# Analog_Signal_Cond.net
KiCad netlist of a schematic drawn in Altium Designer
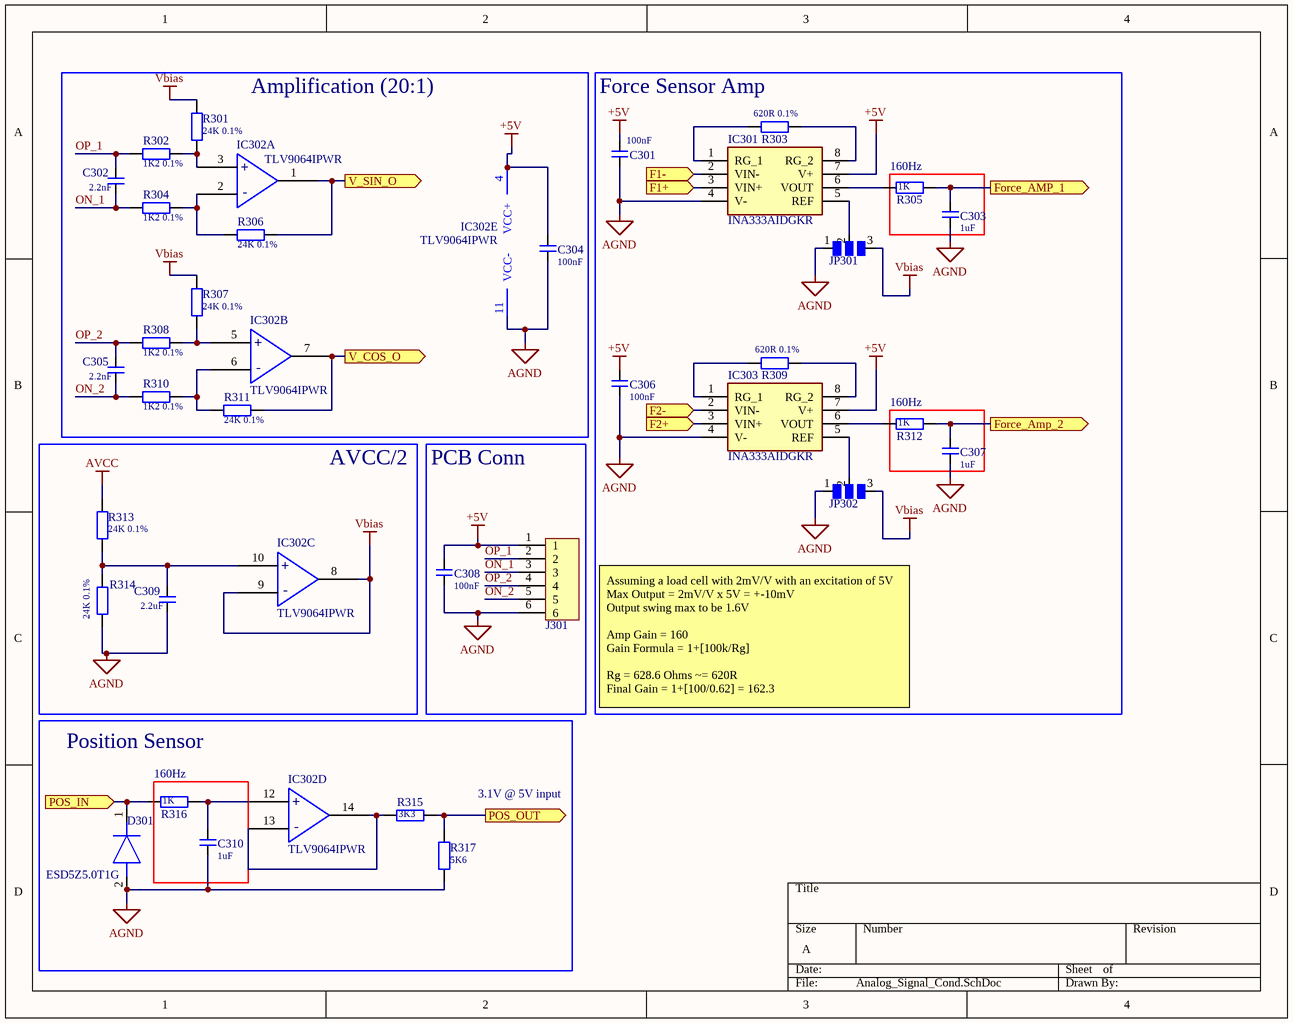
[diagram p0: Analog_Signal_Cond.SchDoc]

(export (version "E")
  (design (tool "Eeschema 10.0.6"))
  (components
    (comp (ref "C301")
      (value "100nF")
      (footprint "CAPC1005X06N")
      (description "Capacitor")
      (fields (field (name "MPN") "GCM155R71H104KE02D") (field (name "Comment") "Cap"))
      (libsource (lib "SamacSys") (part "Cap"))
    )
    (comp (ref "C302")
      (value "2.2nF")
      (footprint "CAPC1608X09N")
      (description "Capacitor")
      (fields (field (name "MPN") "CC0603KRX7R9BB222") (field (name "Comment") "Cap"))
      (libsource (lib "SamacSys") (part "Cap"))
    )
    (comp (ref "C303")
      (value "1uF")
      (footprint "CAPC1005X06N")
      (description "Capacitor")
      (fields (field (name "MPN") "GRM155Z71A105KE01D") (field (name "Comment") "Cap"))
      (libsource (lib "SamacSys") (part "Cap"))
    )
    (comp (ref "C304")
      (value "100nF")
      (footprint "CAPC1005X06N")
      (description "Capacitor")
      (fields (field (name "MPN") "GCM155R71H104KE02D") (field (name "Comment") "Cap"))
      (libsource (lib "SamacSys") (part "Cap"))
    )
    (comp (ref "C305")
      (value "2.2nF")
      (footprint "CAPC1608X09N")
      (description "Capacitor")
      (fields (field (name "MPN") "CC0603KRX7R9BB222") (field (name "Comment") "Cap"))
      (libsource (lib "SamacSys") (part "Cap"))
    )
    (comp (ref "C306")
      (value "100nF")
      (footprint "CAPC1005X06N")
      (description "Capacitor")
      (fields (field (name "MPN") "GCM155R71H104KE02D") (field (name "Comment") "Cap"))
      (libsource (lib "SamacSys") (part "Cap"))
    )
    (comp (ref "C307")
      (value "1uF")
      (footprint "CAPC1005X06N")
      (description "Capacitor")
      (fields (field (name "MPN") "GRM155Z71A105KE01D") (field (name "Comment") "Cap"))
      (libsource (lib "SamacSys") (part "Cap"))
    )
    (comp (ref "C308")
      (value "100nF")
      (footprint "CAPC1005X06N")
      (description "Capacitor")
      (fields (field (name "MPN") "GCM155R71H104KE02D") (field (name "Comment") "Cap"))
      (libsource (lib "SamacSys") (part "Cap"))
    )
    (comp (ref "C309")
      (value "2.2uF")
      (footprint "CAPC1005X06N")
      (description "Capacitor")
      (fields (field (name "MPN") "GRM155Z71A225KE44D") (field (name "Comment") "Cap"))
      (libsource (lib "SamacSys") (part "Cap"))
    )
    (comp (ref "C310")
      (value "1uF")
      (footprint "CAPC1005X06N")
      (description "Capacitor")
      (fields (field (name "MPN") "GRM155Z71A105KE01D") (field (name "Comment") "Cap"))
      (libsource (lib "SamacSys") (part "Cap"))
    )
    (comp (ref "D301")
      (value "ESD5Z5.0T1G")
      (footprint "SamacSys:SODFL1608X70N")
      (description "Diode")
      (fields (field (name "MOUSER PART NUMBER") "863-ESD5Z5.0T1G"))
      (libsource (lib "SamacSys") (part "ESD5Z5.0T1G"))
    )
    (comp (ref "IC301")
      (value "INA333AIDGKR")
      (footprint "SamacSys:SOP65P490X110-8N")
      (description "Integrated Circuit")
      (fields (field (name "MOUSER PART NUMBER") "595-INA333AIDGKR"))
      (libsource (lib "*") (part "INA333AIDGKR"))
    )
    (comp (ref "IC302")
      (value "TLV9064IPWR")
      (footprint "SamacSys:SOP65P640X120-14N")
      (description "Integrated Circuit")
      (fields (field (name "MOUSER PART NUMBER") "595-TLV9064IPWR"))
      (libsource (lib "SamacSys") (part "TLV9064IPWR"))
    )
    (comp (ref "IC303")
      (value "INA333AIDGKR")
      (footprint "SamacSys:SOP65P490X110-8N")
      (description "Integrated Circuit")
      (fields (field (name "MOUSER PART NUMBER") "595-INA333AIDGKR"))
      (libsource (lib "*") (part "INA333AIDGKR"))
    )
    (comp (ref "J301")
      (value "PCB_Conn_6P")
      (footprint "PCB_CONN_6")
      (libsource (lib "SamacSys") (part "PCB_Conn_6P"))
    )
    (comp (ref "JP301")
      (value "Jumper_3")
      (footprint "Jumper_3")
      (libsource (lib "SamacSys") (part "Jumper_3"))
    )
    (comp (ref "JP302")
      (value "Jumper_3")
      (footprint "Jumper_3")
      (libsource (lib "SamacSys") (part "Jumper_3"))
    )
    (comp (ref "R301")
      (value "24K 0.1%")
      (footprint "RESC1005X04N")
      (description "Resistor")
      (fields (field (name "MPN") "AR02BTD2402") (field (name "Comment") "R"))
      (libsource (lib "SamacSys") (part "R"))
    )
    (comp (ref "R302")
      (value "1K2 0.1%")
      (footprint "RESC1005X04N")
      (description "Resistor")
      (fields (field (name "MPN") "RT0603BRD071K2L") (field (name "Comment") "R"))
      (libsource (lib "") (part "R_1"))
    )
    (comp (ref "R303")
      (value "620R 0.1%")
      (footprint "RESC1005X04N")
      (description "Resistor")
      (fields (field (name "MPN") "RT0402BRD0710KL") (field (name "Comment") "R"))
      (libsource (lib "") (part "R_1"))
    )
    (comp (ref "R304")
      (value "1K2 0.1%")
      (footprint "RESC1005X04N")
      (description "Resistor")
      (fields (field (name "MPN") "RT0603BRD071K2L") (field (name "Comment") "R"))
      (libsource (lib "") (part "R_1"))
    )
    (comp (ref "R305")
      (value "1K")
      (footprint "RESC1005X04N")
      (description "Resistor")
      (fields (field (name "MPN") "RC0402FR-071KL") (field (name "Comment") "R"))
      (libsource (lib "") (part "R_1"))
    )
    (comp (ref "R306")
      (value "24K 0.1%")
      (footprint "RESC1005X04N")
      (description "Resistor")
      (fields (field (name "MPN") "AR02BTD2402") (field (name "Comment") "R"))
      (libsource (lib "") (part "R_2"))
    )
    (comp (ref "R307")
      (value "24K 0.1%")
      (footprint "RESC1005X04N")
      (description "Resistor")
      (fields (field (name "MPN") "AR02BTD2402") (field (name "Comment") "R"))
      (libsource (lib "") (part "R_3"))
    )
    (comp (ref "R308")
      (value "1K2 0.1%")
      (footprint "RESC1005X04N")
      (description "Resistor")
      (fields (field (name "MPN") "RT0603BRD071K2L") (field (name "Comment") "R"))
      (libsource (lib "") (part "R_1"))
    )
    (comp (ref "R309")
      (value "620R 0.1%")
      (footprint "RESC1005X04N")
      (description "Resistor")
      (fields (field (name "MPN") "RT0402BRD0710KL") (field (name "Comment") "R"))
      (libsource (lib "") (part "R_1"))
    )
    (comp (ref "R310")
      (value "1K2 0.1%")
      (footprint "RESC1005X04N")
      (description "Resistor")
      (fields (field (name "MPN") "RT0603BRD071K2L") (field (name "Comment") "R"))
      (libsource (lib "") (part "R_1"))
    )
    (comp (ref "R311")
      (value "24K 0.1%")
      (footprint "RESC1005X04N")
      (description "Resistor")
      (fields (field (name "MPN") "AR02BTD2402") (field (name "Comment") "R"))
      (libsource (lib "") (part "R_2"))
    )
    (comp (ref "R312")
      (value "1K")
      (footprint "RESC1005X04N")
      (description "Resistor")
      (fields (field (name "MPN") "RC0402FR-071KL") (field (name "Comment") "R"))
      (libsource (lib "") (part "R_1"))
    )
    (comp (ref "R313")
      (value "24K 0.1%")
      (footprint "RESC1005X04N")
      (description "Resistor")
      (fields (field (name "MPN") "AR02BTD2402") (field (name "Comment") "R"))
      (libsource (lib "") (part "R_3"))
    )
    (comp (ref "R314")
      (value "24K 0.1%")
      (footprint "RESC1005X04N")
      (description "Resistor")
      (fields (field (name "MPN") "AR02BTD2402") (field (name "Comment") "R"))
      (libsource (lib "") (part "R_3"))
    )
    (comp (ref "R315")
      (value "3K3")
      (footprint "RESC1005X04N")
      (description "Resistor")
      (fields (field (name "MPN") "RC0402FR-073K3L") (field (name "Comment") "R"))
      (libsource (lib "") (part "R_1"))
    )
    (comp (ref "R316")
      (value "1K")
      (footprint "RESC1005X04N")
      (description "Resistor")
      (fields (field (name "MPN") "RC0402FR-071KL") (field (name "Comment") "R"))
      (libsource (lib "") (part "R_1"))
    )
    (comp (ref "R317")
      (value "5K6")
      (footprint "RESC1005X04N")
      (description "Resistor")
      (fields (field (name "MPN") "RC0402FR-075K6L") (field (name "Comment") "R"))
      (libsource (lib "SamacSys") (part "R"))
    )
  )
  (nets
    (net (code "1") (name "+5V") (class "Default")
      (node (ref "C301") (pin "2") (pinfunction "2_2") (pintype "passive"))
      (node (ref "C304") (pin "2") (pinfunction "2_2") (pintype "passive"))
      (node (ref "C306") (pin "2") (pinfunction "2_2") (pintype "passive"))
      (node (ref "C308") (pin "2") (pinfunction "2_2") (pintype "passive"))
      (node (ref "IC301") (pin "7") (pinfunction "V+_7") (pintype "passive"))
      (node (ref "IC302") (pin "4") (pinfunction "VCC+_4") (pintype "passive"))
      (node (ref "IC303") (pin "7") (pinfunction "V+_7") (pintype "passive"))
      (node (ref "J301") (pin "1") (pinfunction "1_1") (pintype "passive"))
    )
    (net (code "2") (name "/F1+") (class "Default")
      (node (ref "IC301") (pin "3") (pinfunction "VIN+_3") (pintype "passive"))
    )
    (net (code "3") (name "/F1-") (class "Default")
      (node (ref "IC301") (pin "2") (pinfunction "VIN-_2") (pintype "passive"))
    )
    (net (code "4") (name "/F2+") (class "Default")
      (node (ref "IC303") (pin "3") (pinfunction "VIN+_3") (pintype "passive"))
    )
    (net (code "5") (name "/F2-") (class "Default")
      (node (ref "IC303") (pin "2") (pinfunction "VIN-_2") (pintype "passive"))
    )
    (net (code "6") (name "/Force_AMP_1") (class "Default")
      (node (ref "C303") (pin "1") (pinfunction "1_1") (pintype "passive"))
      (node (ref "R305") (pin "1") (pinfunction "1_1") (pintype "passive"))
    )
    (net (code "7") (name "/Force_Amp_2") (class "Default")
      (node (ref "C307") (pin "1") (pinfunction "1_1") (pintype "passive"))
      (node (ref "R312") (pin "1") (pinfunction "1_1") (pintype "passive"))
    )
    (net (code "8") (name "/ON_1") (class "Default")
      (node (ref "C302") (pin "1") (pinfunction "1_1") (pintype "passive"))
      (node (ref "J301") (pin "3") (pinfunction "3_3") (pintype "passive"))
      (node (ref "R304") (pin "2") (pinfunction "2_2") (pintype "passive"))
    )
    (net (code "9") (name "/ON_2") (class "Default")
      (node (ref "C305") (pin "1") (pinfunction "1_1") (pintype "passive"))
      (node (ref "J301") (pin "5") (pinfunction "5_5") (pintype "passive"))
      (node (ref "R310") (pin "2") (pinfunction "2_2") (pintype "passive"))
    )
    (net (code "10") (name "/OP_1") (class "Default")
      (node (ref "C302") (pin "2") (pinfunction "2_2") (pintype "passive"))
      (node (ref "J301") (pin "2") (pinfunction "2_2") (pintype "passive"))
      (node (ref "R302") (pin "2") (pinfunction "2_2") (pintype "passive"))
    )
    (net (code "11") (name "/OP_2") (class "Default")
      (node (ref "C305") (pin "2") (pinfunction "2_2") (pintype "passive"))
      (node (ref "J301") (pin "4") (pinfunction "4_4") (pintype "passive"))
      (node (ref "R308") (pin "2") (pinfunction "2_2") (pintype "passive"))
    )
    (net (code "12") (name "/POS_IN") (class "Default")
      (node (ref "D301") (pin "1") (pinfunction "K_1") (pintype "passive"))
      (node (ref "R316") (pin "2") (pinfunction "2_2") (pintype "passive"))
    )
    (net (code "13") (name "/POS_OUT") (class "Default")
      (node (ref "R315") (pin "1") (pinfunction "1_1") (pintype "passive"))
      (node (ref "R317") (pin "1") (pinfunction "1_1") (pintype "passive"))
    )
    (net (code "14") (name "/V_COS_O") (class "Default")
      (node (ref "IC302") (pin "7") (pinfunction "OUTB_7") (pintype "passive"))
      (node (ref "R311") (pin "2") (pinfunction "2_2") (pintype "passive"))
    )
    (net (code "15") (name "/V_SIN_O") (class "Default")
      (node (ref "IC302") (pin "1") (pinfunction "OUTA_1") (pintype "passive"))
      (node (ref "R306") (pin "2") (pinfunction "2_2") (pintype "passive"))
    )
    (net (code "16") (name "AGND") (class "Default")
      (node (ref "C301") (pin "1") (pinfunction "1_1") (pintype "passive"))
      (node (ref "C303") (pin "2") (pinfunction "2_2") (pintype "passive"))
      (node (ref "C304") (pin "1") (pinfunction "1_1") (pintype "passive"))
      (node (ref "C306") (pin "1") (pinfunction "1_1") (pintype "passive"))
      (node (ref "C307") (pin "2") (pinfunction "2_2") (pintype "passive"))
      (node (ref "C308") (pin "1") (pinfunction "1_1") (pintype "passive"))
      (node (ref "C309") (pin "1") (pinfunction "1_1") (pintype "passive"))
      (node (ref "C310") (pin "2") (pinfunction "2_2") (pintype "passive"))
      (node (ref "D301") (pin "2") (pinfunction "A_2") (pintype "passive"))
      (node (ref "IC301") (pin "4") (pinfunction "V-_4") (pintype "passive"))
      (node (ref "IC302") (pin "11") (pinfunction "VCC-_11") (pintype "passive"))
      (node (ref "IC303") (pin "4") (pinfunction "V-_4") (pintype "passive"))
      (node (ref "J301") (pin "6") (pinfunction "6_6") (pintype "passive"))
      (node (ref "JP301") (pin "1") (pintype "passive"))
      (node (ref "JP302") (pin "1") (pintype "passive"))
      (node (ref "R314") (pin "1") (pinfunction "1_1") (pintype "passive"))
      (node (ref "R317") (pin "2") (pinfunction "2_2") (pintype "passive"))
    )
    (net (code "17") (name "AVCC") (class "Default")
      (node (ref "R313") (pin "2") (pinfunction "2_2") (pintype "passive"))
    )
    (net (code "18") (name "Net-(IC301-REF)") (class "Default")
      (node (ref "IC301") (pin "5") (pinfunction "REF_5") (pintype "passive"))
      (node (ref "JP301") (pin "2") (pintype "passive"))
    )
    (net (code "19") (name "Net-(IC301-RG_1)") (class "Default")
      (node (ref "IC301") (pin "1") (pinfunction "RG_1_1") (pintype "passive"))
      (node (ref "R303") (pin "2") (pinfunction "2_2") (pintype "passive"))
    )
    (net (code "20") (name "Net-(IC301-RG_2)") (class "Default")
      (node (ref "IC301") (pin "8") (pinfunction "RG_2_8") (pintype "passive"))
      (node (ref "R303") (pin "1") (pinfunction "1_1") (pintype "passive"))
    )
    (net (code "21") (name "Net-(IC301-VOUT)") (class "Default")
      (node (ref "IC301") (pin "6") (pinfunction "VOUT_6") (pintype "passive"))
      (node (ref "R305") (pin "2") (pinfunction "2_2") (pintype "passive"))
    )
    (net (code "22") (name "Net-(IC302A-IN-A)") (class "Default")
      (node (ref "IC302") (pin "2") (pinfunction "IN-A_2") (pintype "passive"))
      (node (ref "R304") (pin "1") (pinfunction "1_1") (pintype "passive"))
      (node (ref "R306") (pin "1") (pinfunction "1_1") (pintype "passive"))
    )
    (net (code "23") (name "Net-(IC302A-In+A)") (class "Default")
      (node (ref "IC302") (pin "3") (pinfunction "In+A_3") (pintype "passive"))
      (node (ref "R301") (pin "2") (pinfunction "2_2") (pintype "passive"))
      (node (ref "R302") (pin "1") (pinfunction "1_1") (pintype "passive"))
    )
    (net (code "24") (name "Net-(IC302B-IN-B)") (class "Default")
      (node (ref "IC302") (pin "6") (pinfunction "IN-B_6") (pintype "passive"))
      (node (ref "R310") (pin "1") (pinfunction "1_1") (pintype "passive"))
      (node (ref "R311") (pin "1") (pinfunction "1_1") (pintype "passive"))
    )
    (net (code "25") (name "Net-(IC302B-In+B)") (class "Default")
      (node (ref "IC302") (pin "5") (pinfunction "In+B_5") (pintype "passive"))
      (node (ref "R307") (pin "1") (pinfunction "1_1") (pintype "passive"))
      (node (ref "R308") (pin "1") (pinfunction "1_1") (pintype "passive"))
    )
    (net (code "26") (name "Net-(IC302C-In+C)") (class "Default")
      (node (ref "C309") (pin "2") (pinfunction "2_2") (pintype "passive"))
      (node (ref "IC302") (pin "10") (pinfunction "In+C_10") (pintype "passive"))
      (node (ref "R313") (pin "1") (pinfunction "1_1") (pintype "passive"))
      (node (ref "R314") (pin "2") (pinfunction "2_2") (pintype "passive"))
    )
    (net (code "27") (name "Net-(IC302D-IN-D)") (class "Default")
      (node (ref "IC302") (pin "13") (pinfunction "IN-D_13") (pintype "passive"))
      (node (ref "IC302") (pin "14") (pinfunction "OUTD_14") (pintype "passive"))
      (node (ref "R315") (pin "2") (pinfunction "2_2") (pintype "passive"))
    )
    (net (code "28") (name "Net-(IC302D-In+D)") (class "Default")
      (node (ref "C310") (pin "1") (pinfunction "1_1") (pintype "passive"))
      (node (ref "IC302") (pin "12") (pinfunction "In+D_12") (pintype "passive"))
      (node (ref "R316") (pin "1") (pinfunction "1_1") (pintype "passive"))
    )
    (net (code "29") (name "Net-(IC303-REF)") (class "Default")
      (node (ref "IC303") (pin "5") (pinfunction "REF_5") (pintype "passive"))
      (node (ref "JP302") (pin "2") (pintype "passive"))
    )
    (net (code "30") (name "Net-(IC303-RG_1)") (class "Default")
      (node (ref "IC303") (pin "1") (pinfunction "RG_1_1") (pintype "passive"))
      (node (ref "R309") (pin "2") (pinfunction "2_2") (pintype "passive"))
    )
    (net (code "31") (name "Net-(IC303-RG_2)") (class "Default")
      (node (ref "IC303") (pin "8") (pinfunction "RG_2_8") (pintype "passive"))
      (node (ref "R309") (pin "1") (pinfunction "1_1") (pintype "passive"))
    )
    (net (code "32") (name "Net-(IC303-VOUT)") (class "Default")
      (node (ref "IC303") (pin "6") (pinfunction "VOUT_6") (pintype "passive"))
      (node (ref "R312") (pin "2") (pinfunction "2_2") (pintype "passive"))
    )
    (net (code "33") (name "Vbias") (class "Default")
      (node (ref "IC302") (pin "8") (pinfunction "OUTC_8") (pintype "passive"))
      (node (ref "IC302") (pin "9") (pinfunction "IN-C_9") (pintype "passive"))
      (node (ref "JP301") (pin "3") (pintype "passive"))
      (node (ref "JP302") (pin "3") (pintype "passive"))
      (node (ref "R301") (pin "1") (pinfunction "1_1") (pintype "passive"))
      (node (ref "R307") (pin "2") (pinfunction "2_2") (pintype "passive"))
    )
  )
)
